# Adafruit_Ultimate_GPS_Flora.net
KiCad netlist of a schematic drawn in EAGLE
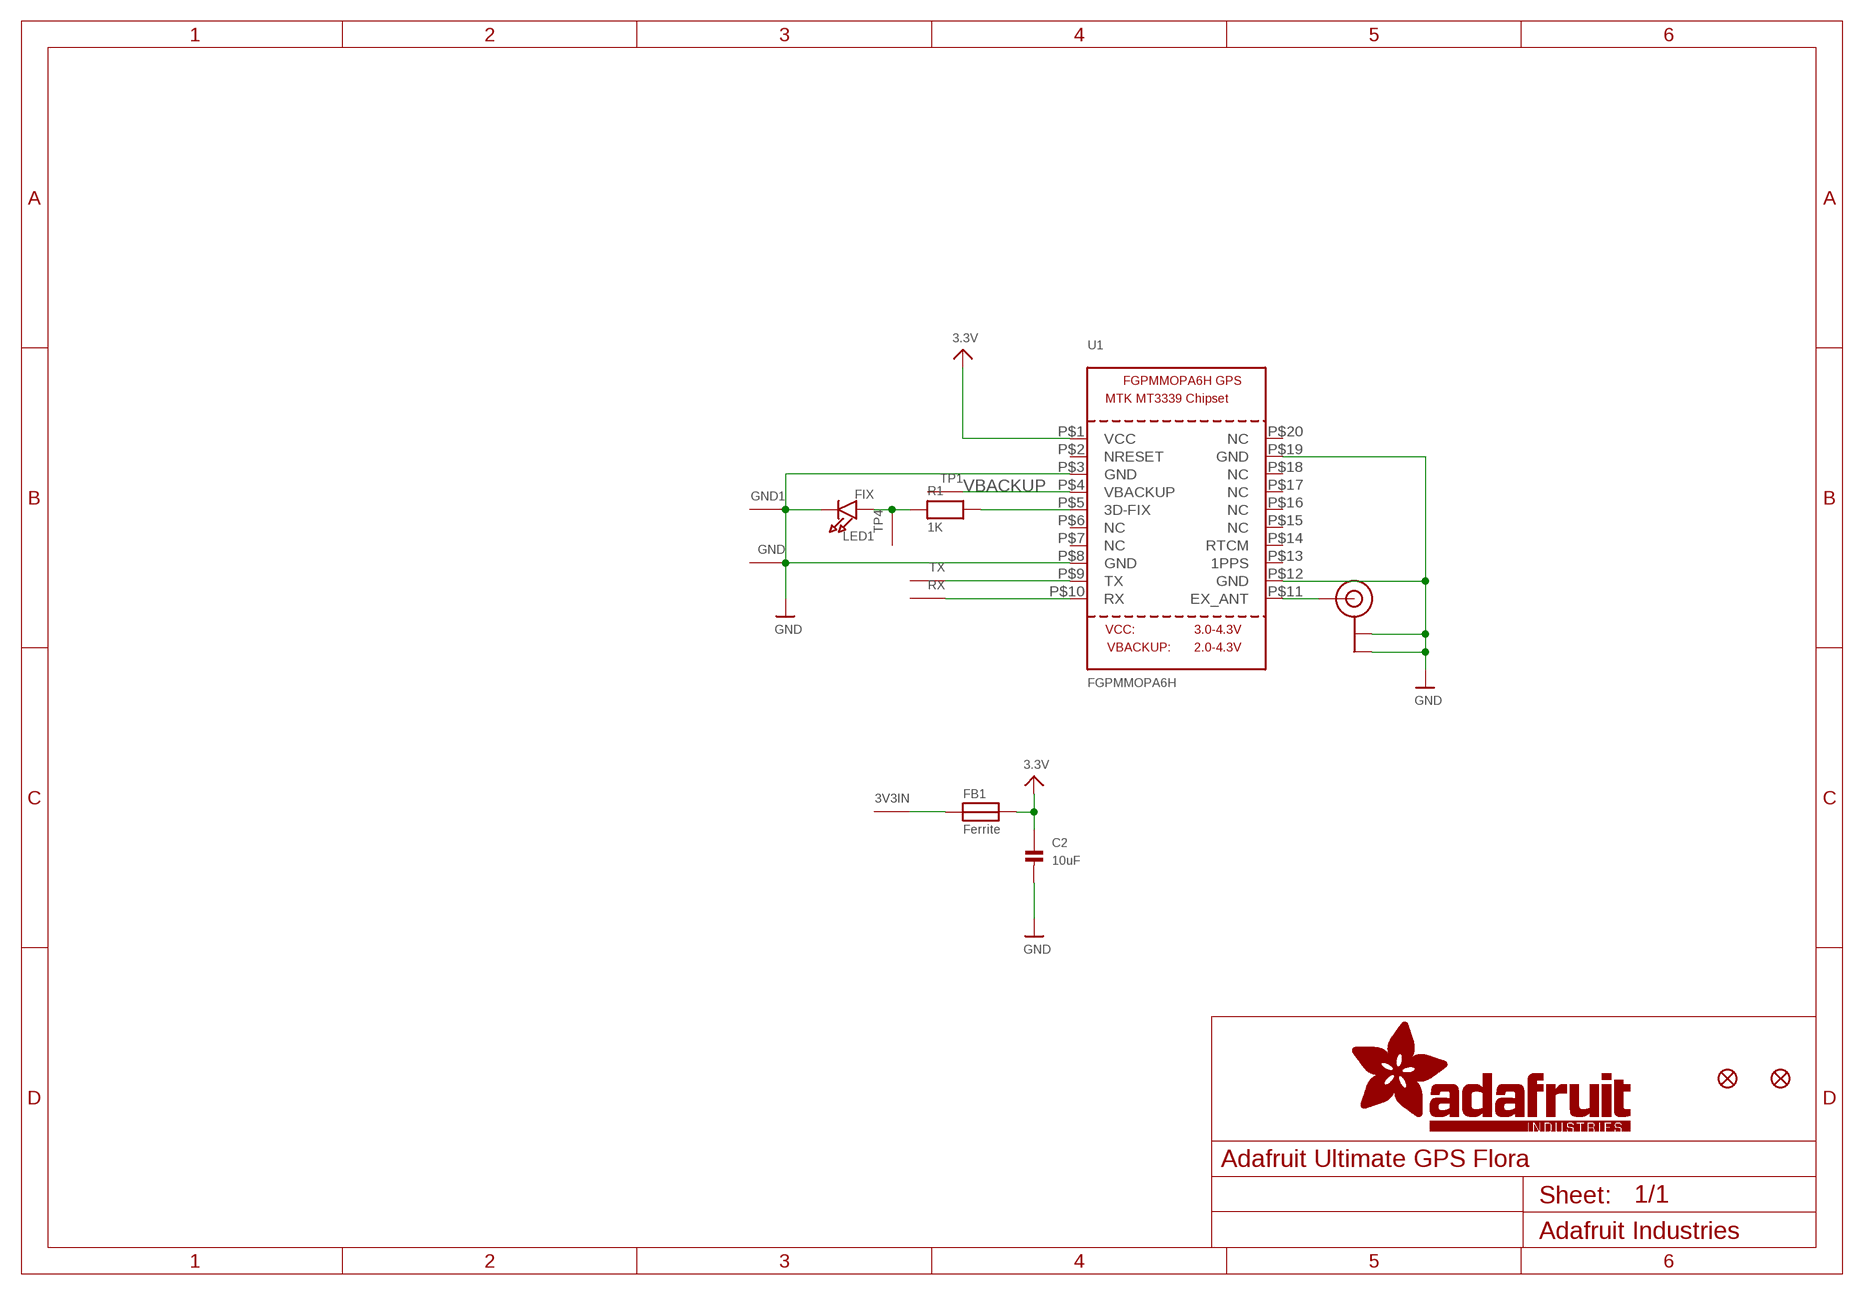
[diagram p0: schematic, sheet 1]

(export (version "E")
  (design (tool "Eeschema 10.0.6"))
  (components
    (comp (ref "3V3IN")
      (value "SEWTAP-2.0IN")
      (footprint "eagle-import:SEWINGTAP_2.0")
      (libsource (lib "eagle-import") (part "SEWTAP-2.0IN"))
    )
    (comp (ref "C2")
      (value "10uF")
      (footprint "eagle-import:0805")
      (libsource (lib "eagle-import") (part "CAP_CERAMIC0805"))
    )
    (comp (ref "FB1")
      (value "Ferrite")
      (footprint "eagle-import:0805")
      (libsource (lib "eagle-import") (part "FERRITE0805"))
    )
    (comp (ref "FID1")
      (value "FIDUCIAL\"\"")
      (footprint "eagle-import:FIDUCIAL_1MM")
      (libsource (lib "eagle-import") (part "FIDUCIAL{dblquote}{dblquote}"))
    )
    (comp (ref "FID2")
      (value "FIDUCIAL\"\"")
      (footprint "eagle-import:FIDUCIAL_1MM")
      (libsource (lib "eagle-import") (part "FIDUCIAL{dblquote}{dblquote}"))
    )
    (comp (ref "GND")
      (value "SEWTAP-2.0IN")
      (footprint "eagle-import:SEWINGTAP_2.0")
      (libsource (lib "eagle-import") (part "SEWTAP-2.0IN"))
    )
    (comp (ref "GND1")
      (value "SEWTAP-2.0IN")
      (footprint "eagle-import:SEWINGTAP_2.0")
      (libsource (lib "eagle-import") (part "SEWTAP-2.0IN"))
    )
    (comp (ref "LED1")
      (value "FIX")
      (footprint "eagle-import:CHIPLED_0805")
      (libsource (lib "eagle-import") (part "LED0805"))
    )
    (comp (ref "R1")
      (value "1K")
      (footprint "eagle-import:0805")
      (libsource (lib "eagle-import") (part "RESISTOR0805"))
    )
    (comp (ref "RX")
      (value "SEWTAP-2.0IN")
      (footprint "eagle-import:SEWINGTAP_2.0")
      (libsource (lib "eagle-import") (part "SEWTAP-2.0IN"))
    )
    (comp (ref "TP1")
      (value "SEWTAP-2.0IN")
      (footprint "eagle-import:SEWINGTAP_2.0")
      (libsource (lib "eagle-import") (part "SEWTAP-2.0IN"))
    )
    (comp (ref "TP4")
      (value "SEWTAP-2.0IN")
      (footprint "eagle-import:SEWINGTAP_2.0")
      (libsource (lib "eagle-import") (part "SEWTAP-2.0IN"))
    )
    (comp (ref "TX")
      (value "SEWTAP-2.0IN")
      (footprint "eagle-import:SEWINGTAP_2.0")
      (libsource (lib "eagle-import") (part "SEWTAP-2.0IN"))
    )
    (comp (ref "U$20")
      (value "U.FL")
      (footprint "eagle-import:U.FL")
      (libsource (lib "eagle-import") (part "U.FL"))
    )
    (comp (ref "U1")
      (value "FGPMMOPA6H")
      (footprint "eagle-import:FGPMMOPA6H")
      (libsource (lib "eagle-import") (part "GPS_FGPMMOPA6H"))
    )
  )
  (nets
    (net (code "1") (name "/VBACKUP") (class "Default")
      (node (ref "TP1") (pin "P$1") (pinfunction "SEW_P$1") (pintype "bidirectional"))
      (node (ref "U1") (pin "P$4") (pinfunction "VBACKUP_P$4") (pintype "bidirectional"))
    )
    (net (code "2") (name "3.3V") (class "Default")
      (node (ref "C2") (pin "1") (pinfunction "P$1_1") (pintype "passive"))
      (node (ref "FB1") (pin "2") (pinfunction "P$2_2") (pintype "bidirectional"))
      (node (ref "U1") (pin "P$1") (pinfunction "VCC_P$1") (pintype "bidirectional"))
    )
    (net (code "3") (name "GND") (class "Default")
      (node (ref "C2") (pin "2") (pinfunction "P$2_2") (pintype "passive"))
      (node (ref "GND") (pin "P$1") (pinfunction "SEW_P$1") (pintype "bidirectional"))
      (node (ref "GND1") (pin "P$1") (pinfunction "SEW_P$1") (pintype "bidirectional"))
      (node (ref "LED1") (pin "C") (pinfunction "C_C") (pintype "passive"))
      (node (ref "U$20") (pin "P$1") (pinfunction "GND_P$1") (pintype "bidirectional"))
      (node (ref "U$20") (pin "P$2") (pinfunction "GND_P$2") (pintype "bidirectional"))
      (node (ref "U1") (pin "P$12") (pinfunction "GND_P$12") (pintype "bidirectional"))
      (node (ref "U1") (pin "P$19") (pinfunction "GND_P$19") (pintype "bidirectional"))
      (node (ref "U1") (pin "P$3") (pinfunction "GND_P$3") (pintype "bidirectional"))
      (node (ref "U1") (pin "P$8") (pinfunction "GND_P$8") (pintype "bidirectional"))
    )
    (net (code "4") (name "Net-(3V3IN-SEW)") (class "Default")
      (node (ref "3V3IN") (pin "P$1") (pinfunction "SEW_P$1") (pintype "bidirectional"))
      (node (ref "FB1") (pin "1") (pinfunction "P$1_1") (pintype "bidirectional"))
    )
    (net (code "5") (name "Net-(RX-SEW)") (class "Default")
      (node (ref "RX") (pin "P$1") (pinfunction "SEW_P$1") (pintype "bidirectional"))
      (node (ref "U1") (pin "P$10") (pinfunction "RX_P$10") (pintype "bidirectional"))
    )
    (net (code "6") (name "Net-(TP4-SEW)") (class "Default")
      (node (ref "LED1") (pin "A") (pinfunction "A_A") (pintype "passive"))
      (node (ref "R1") (pin "1") (pinfunction "1_1") (pintype "passive"))
      (node (ref "TP4") (pin "P$1") (pinfunction "SEW_P$1") (pintype "bidirectional"))
    )
    (net (code "7") (name "Net-(TX-SEW)") (class "Default")
      (node (ref "TX") (pin "P$1") (pinfunction "SEW_P$1") (pintype "bidirectional"))
      (node (ref "U1") (pin "P$9") (pinfunction "TX_P$9") (pintype "bidirectional"))
    )
    (net (code "8") (name "Net-(U$20-SIGNAL)") (class "Default")
      (node (ref "U$20") (pin "P$3") (pinfunction "SIGNAL_P$3") (pintype "bidirectional"))
      (node (ref "U1") (pin "P$11") (pinfunction "EX_ANT_P$11") (pintype "bidirectional"))
    )
    (net (code "9") (name "Net-(U1-3D-FIX)") (class "Default")
      (node (ref "R1") (pin "2") (pinfunction "2_2") (pintype "passive"))
      (node (ref "U1") (pin "P$5") (pinfunction "3D-FIX_P$5") (pintype "bidirectional"))
    )
    (net (code "10") (name "unconnected-(U1-1PPS-PadP$13)") (class "Default")
      (node (ref "U1") (pin "P$13") (pinfunction "1PPS_P$13") (pintype "bidirectional"))
    )
    (net (code "11") (name "unconnected-(U1-NC-PadP$6)") (class "Default")
      (node (ref "U1") (pin "P$6") (pinfunction "NC_P$6") (pintype "bidirectional"))
    )
    (net (code "12") (name "unconnected-(U1-NC-PadP$7)") (class "Default")
      (node (ref "U1") (pin "P$7") (pinfunction "NC_P$7") (pintype "bidirectional"))
    )
    (net (code "13") (name "unconnected-(U1-NC-PadP$15)") (class "Default")
      (node (ref "U1") (pin "P$15") (pinfunction "NC_P$15") (pintype "bidirectional"))
    )
    (net (code "14") (name "unconnected-(U1-NC-PadP$16)") (class "Default")
      (node (ref "U1") (pin "P$16") (pinfunction "NC_P$16") (pintype "bidirectional"))
    )
    (net (code "15") (name "unconnected-(U1-NC-PadP$17)") (class "Default")
      (node (ref "U1") (pin "P$17") (pinfunction "NC_P$17") (pintype "bidirectional"))
    )
    (net (code "16") (name "unconnected-(U1-NC-PadP$18)") (class "Default")
      (node (ref "U1") (pin "P$18") (pinfunction "NC_P$18") (pintype "bidirectional"))
    )
    (net (code "17") (name "unconnected-(U1-NC-PadP$20)") (class "Default")
      (node (ref "U1") (pin "P$20") (pinfunction "NC_P$20") (pintype "bidirectional"))
    )
    (net (code "18") (name "unconnected-(U1-NRESET-PadP$2)") (class "Default")
      (node (ref "U1") (pin "P$2") (pinfunction "NRESET_P$2") (pintype "bidirectional"))
    )
    (net (code "19") (name "unconnected-(U1-RTCM-PadP$14)") (class "Default")
      (node (ref "U1") (pin "P$14") (pinfunction "RTCM_P$14") (pintype "bidirectional"))
    )
  )
)
